# mainv2_2.net
KiCad netlist of a schematic drawn in EAGLE
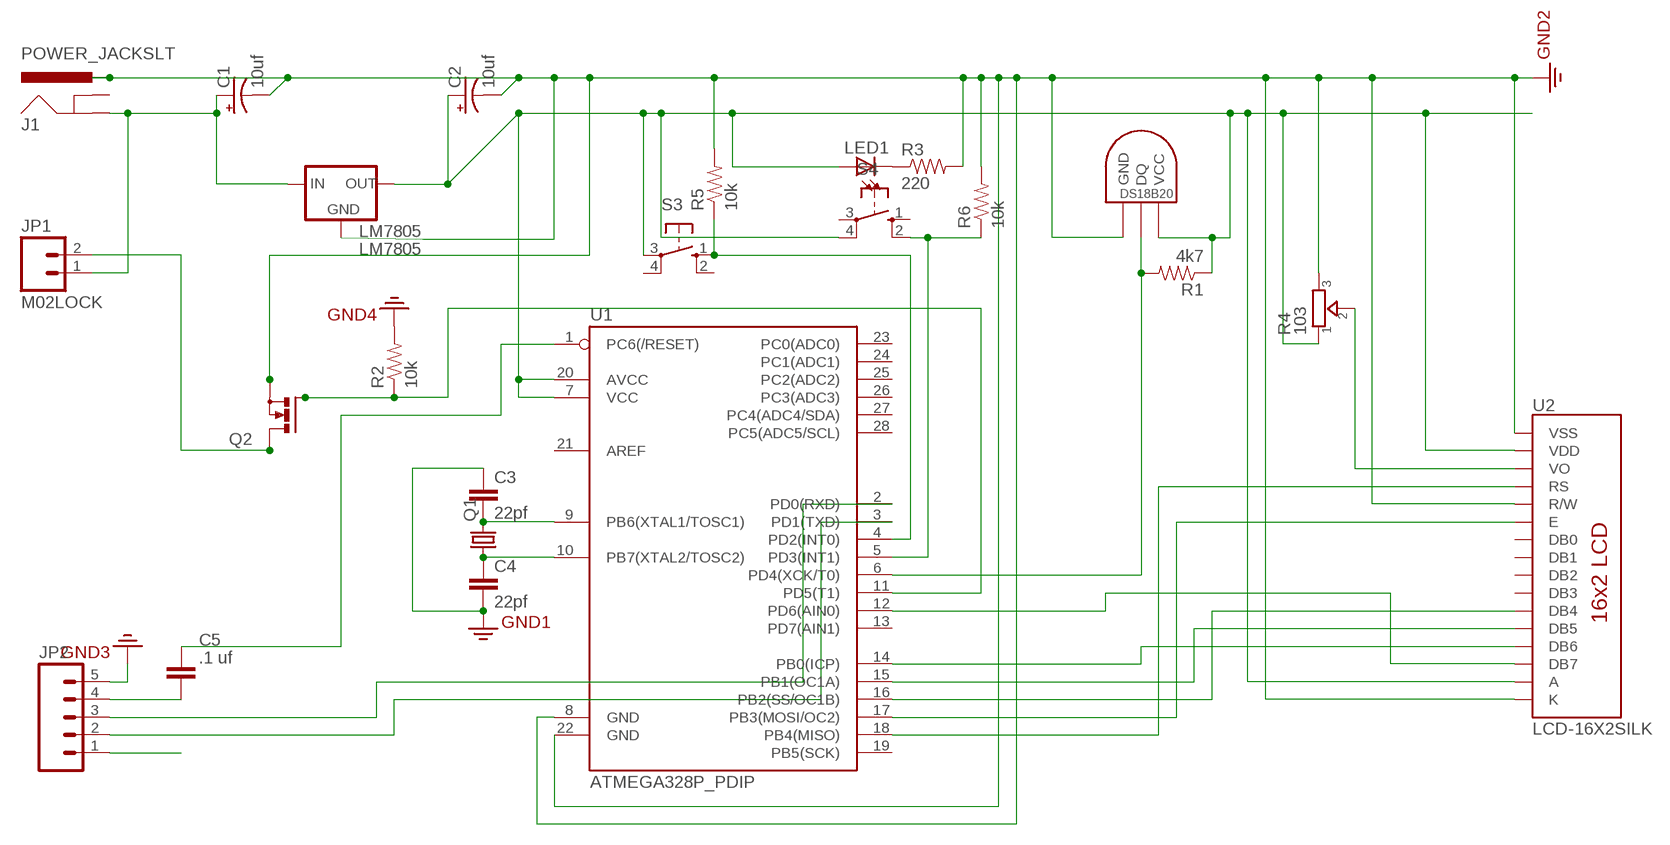
[diagram p0: schematic, sheet 1]

(export (version "E")
  (design (tool "Eeschema 10.0.6"))
  (components
    (comp (ref "C1")
      (value "10uf")
      (footprint "eagle-import:CPOL-RADIAL-10UF-25V")
      (libsource (lib "eagle-import") (part "10UF-25V-20%(PTH)"))
    )
    (comp (ref "C2")
      (value "10uf")
      (footprint "eagle-import:CPOL-RADIAL-10UF-25V")
      (libsource (lib "eagle-import") (part "10UF-25V-20%(PTH)"))
    )
    (comp (ref "C3")
      (value "22pf")
      (footprint "eagle-import:CAP-PTH-SMALL2")
      (libsource (lib "eagle-import") (part "CAPPTH2"))
    )
    (comp (ref "C4")
      (value "22pf")
      (footprint "eagle-import:CAP-PTH-SMALL2")
      (libsource (lib "eagle-import") (part "CAPPTH2"))
    )
    (comp (ref "C5")
      (value ".1 uf")
      (footprint "eagle-import:C0.1PTH")
      (libsource (lib "eagle-import") (part "CAPACITOR_NPOL-PTH_0.1{dblquote}"))
    )
    (comp (ref "J1")
      (value "POWER_JACKSLT")
      (footprint "eagle-import:POWER_JACK_SLOT")
      (libsource (lib "eagle-import") (part "POWER_JACKSLT"))
    )
    (comp (ref "JP1")
      (value "M02LOCK")
      (footprint "eagle-import:1X02_LOCK")
      (libsource (lib "eagle-import") (part "M02LOCK"))
    )
    (comp (ref "JP2")
      (value "M05PTH")
      (footprint "eagle-import:1X05")
      (libsource (lib "eagle-import") (part "M05PTH"))
    )
    (comp (ref "LED1")
      (value "LED3MM")
      (footprint "eagle-import:LED3MM")
      (libsource (lib "eagle-import") (part "LED3MM"))
    )
    (comp (ref "LM7805")
      (value "LM7805")
      (footprint "eagle-import:TO220-IGO")
      (libsource (lib "eagle-import") (part "V_REG_78XXSINK"))
    )
    (comp (ref "Q1")
      (value "CRYSTALHC49S")
      (footprint "eagle-import:HC49_S")
      (libsource (lib "eagle-import") (part "CRYSTALHC49S"))
    )
    (comp (ref "Q2")
      (value "PMOSFET_NTO220BV")
      (footprint "eagle-import:TO220BV")
      (libsource (lib "eagle-import") (part "PMOSFET_NTO220BV"))
    )
    (comp (ref "R1")
      (value "4k7")
      (footprint "eagle-import:AXIAL-0.3")
      (libsource (lib "eagle-import") (part "RESISTORAXIAL-0.3"))
    )
    (comp (ref "R2")
      (value "10k")
      (footprint "eagle-import:AXIAL-0.3")
      (libsource (lib "eagle-import") (part "RESISTORAXIAL-0.3"))
    )
    (comp (ref "R3")
      (value "220")
      (footprint "eagle-import:AXIAL-0.3")
      (libsource (lib "eagle-import") (part "RESISTORAXIAL-0.3"))
    )
    (comp (ref "R4")
      (value "103")
      (footprint "eagle-import:TRIMMER_3306F")
      (libsource (lib "eagle-import") (part "TRIMMER-3306F"))
    )
    (comp (ref "R5")
      (value "10k")
      (footprint "eagle-import:AXIAL-0.3")
      (libsource (lib "eagle-import") (part "RESISTORAXIAL-0.3"))
    )
    (comp (ref "R6")
      (value "10k")
      (footprint "eagle-import:AXIAL-0.3")
      (libsource (lib "eagle-import") (part "RESISTORAXIAL-0.3"))
    )
    (comp (ref "S3")
      (value "10-XX")
      (footprint "eagle-import:B3F-10XX")
      (fields (field (name "MPN") "B3F-1000"))
      (libsource (lib "eagle-import") (part "10-XX"))
    )
    (comp (ref "S4")
      (value "10-XX")
      (footprint "eagle-import:B3F-10XX")
      (fields (field (name "MPN") "B3F-1000"))
      (libsource (lib "eagle-import") (part "10-XX"))
    )
    (comp (ref "U$1")
      (value "DS1820TO92")
      (footprint "eagle-import:DS1820")
      (libsource (lib "eagle-import") (part "DS1820TO92"))
    )
    (comp (ref "U1")
      (value "ATMEGA328P_PDIP")
      (footprint "eagle-import:DIL28-3")
      (libsource (lib "eagle-import") (part "ATMEGA328P_PDIP"))
    )
    (comp (ref "U2")
      (value "LCD-16X2SILK")
      (footprint "eagle-import:LCD-16X2")
      (libsource (lib "eagle-import") (part "LCD-16X2SILK"))
    )
  )
  (nets
    (net (code "1") (name "/VCC") (class "Default")
      (node (ref "C2") (pin "1") (pinfunction "+_1") (pintype "passive"))
      (node (ref "JP2") (pin "1") (pinfunction "1_1") (pintype "passive"))
      (node (ref "LED1") (pin "A") (pinfunction "A_A") (pintype "passive"))
      (node (ref "LM7805") (pin "OUT") (pinfunction "OUT_OUT") (pintype "output"))
      (node (ref "R1") (pin "P$1") (pinfunction "1_P$1") (pintype "passive"))
      (node (ref "R4") (pin "1") (pinfunction "1_1") (pintype "passive"))
      (node (ref "S3") (pin "3") (pinfunction "P_3") (pintype "passive"))
      (node (ref "S4") (pin "4") (pinfunction "P1_4") (pintype "passive"))
      (node (ref "U$1") (pin "VDD") (pinfunction "VCC_VDD") (pintype "power_in"))
      (node (ref "U1") (pin "20") (pinfunction "AVCC_20") (pintype "bidirectional"))
      (node (ref "U1") (pin "7") (pinfunction "VCC_7") (pintype "bidirectional"))
      (node (ref "U2") (pin "15") (pinfunction "A_15") (pintype "power_in"))
      (node (ref "U2") (pin "2") (pinfunction "VDD_2") (pintype "power_in"))
    )
    (net (code "2") (name "GND2") (class "Default")
      (node (ref "C1") (pin "2") (pinfunction "-_2") (pintype "passive"))
      (node (ref "C2") (pin "2") (pinfunction "-_2") (pintype "passive"))
      (node (ref "C3") (pin "1") (pinfunction "1_1") (pintype "passive"))
      (node (ref "C4") (pin "2") (pinfunction "2_2") (pintype "passive"))
      (node (ref "J1") (pin "PWR") (pinfunction "PWR_PWR") (pintype "bidirectional"))
      (node (ref "JP2") (pin "5") (pinfunction "5_5") (pintype "passive"))
      (node (ref "LM7805") (pin "GND") (pinfunction "GND_GND") (pintype "input"))
      (node (ref "Q2") (pin "S") (pinfunction "S_S") (pintype "passive"))
      (node (ref "R2") (pin "P$2") (pinfunction "2_P$2") (pintype "passive"))
      (node (ref "R3") (pin "P$2") (pinfunction "2_P$2") (pintype "passive"))
      (node (ref "R4") (pin "3") (pinfunction "3_3") (pintype "passive"))
      (node (ref "R5") (pin "P$2") (pinfunction "2_P$2") (pintype "passive"))
      (node (ref "R6") (pin "P$2") (pinfunction "2_P$2") (pintype "passive"))
      (node (ref "U$1") (pin "GND") (pinfunction "GND_GND") (pintype "power_in"))
      (node (ref "U1") (pin "22") (pinfunction "GND_22") (pintype "bidirectional"))
      (node (ref "U1") (pin "8") (pinfunction "GND_8") (pintype "bidirectional"))
      (node (ref "U2") (pin "1") (pinfunction "VSS_1") (pintype "power_in"))
      (node (ref "U2") (pin "16") (pinfunction "K_16") (pintype "power_in"))
      (node (ref "U2") (pin "5") (pinfunction "R/W_5") (pintype "input"))
    )
    (net (code "3") (name "Net-(C1-+)") (class "Default")
      (node (ref "C1") (pin "1") (pinfunction "+_1") (pintype "passive"))
      (node (ref "J1") (pin "GND@2") (pinfunction "GND_GND@2") (pintype "bidirectional"))
      (node (ref "JP1") (pin "1") (pinfunction "1_1") (pintype "passive"))
      (node (ref "LM7805") (pin "IN") (pinfunction "IN_IN") (pintype "input"))
    )
    (net (code "4") (name "Net-(C5-Pad2)") (class "Default")
      (node (ref "C5") (pin "2") (pinfunction "2_2") (pintype "passive"))
      (node (ref "JP2") (pin "4") (pinfunction "4_4") (pintype "passive"))
    )
    (net (code "5") (name "Net-(JP1-Pad2)") (class "Default")
      (node (ref "JP1") (pin "2") (pinfunction "2_2") (pintype "passive"))
      (node (ref "Q2") (pin "D") (pinfunction "D_D") (pintype "passive"))
    )
    (net (code "6") (name "Net-(LED1-C)") (class "Default")
      (node (ref "LED1") (pin "K") (pinfunction "C_K") (pintype "passive"))
      (node (ref "R3") (pin "P$1") (pinfunction "1_P$1") (pintype "passive"))
    )
    (net (code "7") (name "Net-(R1-2)") (class "Default")
      (node (ref "R1") (pin "P$2") (pinfunction "2_P$2") (pintype "passive"))
      (node (ref "U$1") (pin "DQ") (pinfunction "DQ_DQ") (pintype "bidirectional"))
      (node (ref "U1") (pin "6") (pinfunction "PD4(XCK/T0)_6") (pintype "bidirectional"))
    )
    (net (code "8") (name "Net-(R2-1)") (class "Default")
      (node (ref "Q2") (pin "G") (pinfunction "G_G") (pintype "passive"))
      (node (ref "R2") (pin "P$1") (pinfunction "1_P$1") (pintype "passive"))
      (node (ref "U1") (pin "11") (pinfunction "PD5(T1)_11") (pintype "bidirectional"))
    )
    (net (code "9") (name "Net-(R5-1)") (class "Default")
      (node (ref "R5") (pin "P$1") (pinfunction "1_P$1") (pintype "passive"))
      (node (ref "S3") (pin "1") (pinfunction "S_1") (pintype "passive"))
      (node (ref "U1") (pin "4") (pinfunction "PD2(INT0)_4") (pintype "bidirectional"))
    )
    (net (code "10") (name "Net-(R6-1)") (class "Default")
      (node (ref "R6") (pin "P$1") (pinfunction "1_P$1") (pintype "passive"))
      (node (ref "S4") (pin "2") (pinfunction "S1_2") (pintype "passive"))
      (node (ref "U1") (pin "5") (pinfunction "PD3(INT1)_5") (pintype "bidirectional"))
    )
    (net (code "11") (name "Net-(U1-PB0(ICP))") (class "Default")
      (node (ref "U1") (pin "14") (pinfunction "PB0(ICP)_14") (pintype "bidirectional"))
      (node (ref "U2") (pin "13") (pinfunction "DB6_13") (pintype "bidirectional"))
    )
    (net (code "12") (name "Net-(U1-PB1(OC1A))") (class "Default")
      (node (ref "U1") (pin "15") (pinfunction "PB1(OC1A)_15") (pintype "bidirectional"))
      (node (ref "U2") (pin "12") (pinfunction "DB5_12") (pintype "bidirectional"))
    )
    (net (code "13") (name "Net-(U1-PB2(SS{slash}OC1B))") (class "Default")
      (node (ref "U1") (pin "16") (pinfunction "PB2(SS/OC1B)_16") (pintype "bidirectional"))
      (node (ref "U2") (pin "11") (pinfunction "DB4_11") (pintype "bidirectional"))
    )
    (net (code "14") (name "Net-(U1-PB3(MOSI{slash}OC2))") (class "Default")
      (node (ref "U1") (pin "17") (pinfunction "PB3(MOSI/OC2)_17") (pintype "bidirectional"))
      (node (ref "U2") (pin "6") (pinfunction "E_6") (pintype "input"))
    )
    (net (code "15") (name "Net-(U1-PB4(MISO))") (class "Default")
      (node (ref "U1") (pin "18") (pinfunction "PB4(MISO)_18") (pintype "bidirectional"))
      (node (ref "U2") (pin "4") (pinfunction "RS_4") (pintype "input"))
    )
    (net (code "16") (name "Net-(U1-PB6(XTAL1{slash}TOSC1))") (class "Default")
      (node (ref "C3") (pin "2") (pinfunction "2_2") (pintype "passive"))
      (node (ref "Q1") (pin "2") (pinfunction "2_2") (pintype "passive"))
      (node (ref "U1") (pin "9") (pinfunction "PB6(XTAL1/TOSC1)_9") (pintype "bidirectional"))
    )
    (net (code "17") (name "Net-(U1-PB7(XTAL2{slash}TOSC2))") (class "Default")
      (node (ref "C4") (pin "1") (pinfunction "1_1") (pintype "passive"))
      (node (ref "Q1") (pin "1") (pinfunction "1_1") (pintype "passive"))
      (node (ref "U1") (pin "10") (pinfunction "PB7(XTAL2/TOSC2)_10") (pintype "bidirectional"))
    )
    (net (code "18") (name "Net-(U1-PC6({slash}RESET))") (class "Default")
      (node (ref "C5") (pin "1") (pinfunction "1_1") (pintype "passive"))
      (node (ref "U1") (pin "1") (pinfunction "PC6(/RESET)_1") (pintype "bidirectional"))
    )
    (net (code "19") (name "Net-(U1-PD0(RXD))") (class "Default")
      (node (ref "JP2") (pin "3") (pinfunction "3_3") (pintype "passive"))
      (node (ref "U1") (pin "2") (pinfunction "PD0(RXD)_2") (pintype "bidirectional"))
    )
    (net (code "20") (name "Net-(U1-PD1(TXD))") (class "Default")
      (node (ref "JP2") (pin "2") (pinfunction "2_2") (pintype "passive"))
      (node (ref "U1") (pin "3") (pinfunction "PD1(TXD)_3") (pintype "bidirectional"))
    )
    (net (code "21") (name "Net-(U1-PD6(AIN0))") (class "Default")
      (node (ref "U1") (pin "12") (pinfunction "PD6(AIN0)_12") (pintype "bidirectional"))
      (node (ref "U2") (pin "14") (pinfunction "DB7_14") (pintype "bidirectional"))
    )
    (net (code "22") (name "Net-(U2-VO)") (class "Default")
      (node (ref "R4") (pin "2") (pinfunction "2_2") (pintype "passive"))
      (node (ref "U2") (pin "3") (pinfunction "VO_3") (pintype "bidirectional"))
    )
    (net (code "23") (name "unconnected-(J1-GNDBREAK-PadGND@1)") (class "Default")
      (node (ref "J1") (pin "GND@1") (pinfunction "GNDBREAK_GND@1") (pintype "bidirectional"))
    )
    (net (code "24") (name "unconnected-(S3-P1-Pad4)") (class "Default")
      (node (ref "S3") (pin "4") (pinfunction "P1_4") (pintype "passive"))
    )
    (net (code "25") (name "unconnected-(S3-S1-Pad2)") (class "Default")
      (node (ref "S3") (pin "2") (pinfunction "S1_2") (pintype "passive"))
    )
    (net (code "26") (name "unconnected-(S4-P-Pad3)") (class "Default")
      (node (ref "S4") (pin "3") (pinfunction "P_3") (pintype "passive"))
    )
    (net (code "27") (name "unconnected-(S4-S-Pad1)") (class "Default")
      (node (ref "S4") (pin "1") (pinfunction "S_1") (pintype "passive"))
    )
    (net (code "28") (name "unconnected-(U1-AREF-Pad21)") (class "Default")
      (node (ref "U1") (pin "21") (pinfunction "AREF_21") (pintype "bidirectional"))
    )
    (net (code "29") (name "unconnected-(U1-PB5(SCK)-Pad19)") (class "Default")
      (node (ref "U1") (pin "19") (pinfunction "PB5(SCK)_19") (pintype "bidirectional"))
    )
    (net (code "30") (name "unconnected-(U1-PC0(ADC0)-Pad23)") (class "Default")
      (node (ref "U1") (pin "23") (pinfunction "PC0(ADC0)_23") (pintype "bidirectional"))
    )
    (net (code "31") (name "unconnected-(U1-PC1(ADC1)-Pad24)") (class "Default")
      (node (ref "U1") (pin "24") (pinfunction "PC1(ADC1)_24") (pintype "bidirectional"))
    )
    (net (code "32") (name "unconnected-(U1-PC2(ADC2)-Pad25)") (class "Default")
      (node (ref "U1") (pin "25") (pinfunction "PC2(ADC2)_25") (pintype "bidirectional"))
    )
    (net (code "33") (name "unconnected-(U1-PC3(ADC3)-Pad26)") (class "Default")
      (node (ref "U1") (pin "26") (pinfunction "PC3(ADC3)_26") (pintype "bidirectional"))
    )
    (net (code "34") (name "unconnected-(U1-PC4(ADC4{slash}SDA)-Pad27)") (class "Default")
      (node (ref "U1") (pin "27") (pinfunction "PC4(ADC4/SDA)_27") (pintype "bidirectional"))
    )
    (net (code "35") (name "unconnected-(U1-PC5(ADC5{slash}SCL)-Pad28)") (class "Default")
      (node (ref "U1") (pin "28") (pinfunction "PC5(ADC5/SCL)_28") (pintype "bidirectional"))
    )
    (net (code "36") (name "unconnected-(U1-PD7(AIN1)-Pad13)") (class "Default")
      (node (ref "U1") (pin "13") (pinfunction "PD7(AIN1)_13") (pintype "bidirectional"))
    )
    (net (code "37") (name "unconnected-(U2-DB0-Pad7)") (class "Default")
      (node (ref "U2") (pin "7") (pinfunction "DB0_7") (pintype "bidirectional"))
    )
    (net (code "38") (name "unconnected-(U2-DB1-Pad8)") (class "Default")
      (node (ref "U2") (pin "8") (pinfunction "DB1_8") (pintype "bidirectional"))
    )
    (net (code "39") (name "unconnected-(U2-DB2-Pad9)") (class "Default")
      (node (ref "U2") (pin "9") (pinfunction "DB2_9") (pintype "bidirectional"))
    )
    (net (code "40") (name "unconnected-(U2-DB3-Pad10)") (class "Default")
      (node (ref "U2") (pin "10") (pinfunction "DB3_10") (pintype "bidirectional"))
    )
  )
)
